# Gastroscopy-CutController_Button.net
KiCad netlist of a schematic drawn in Altium Designer
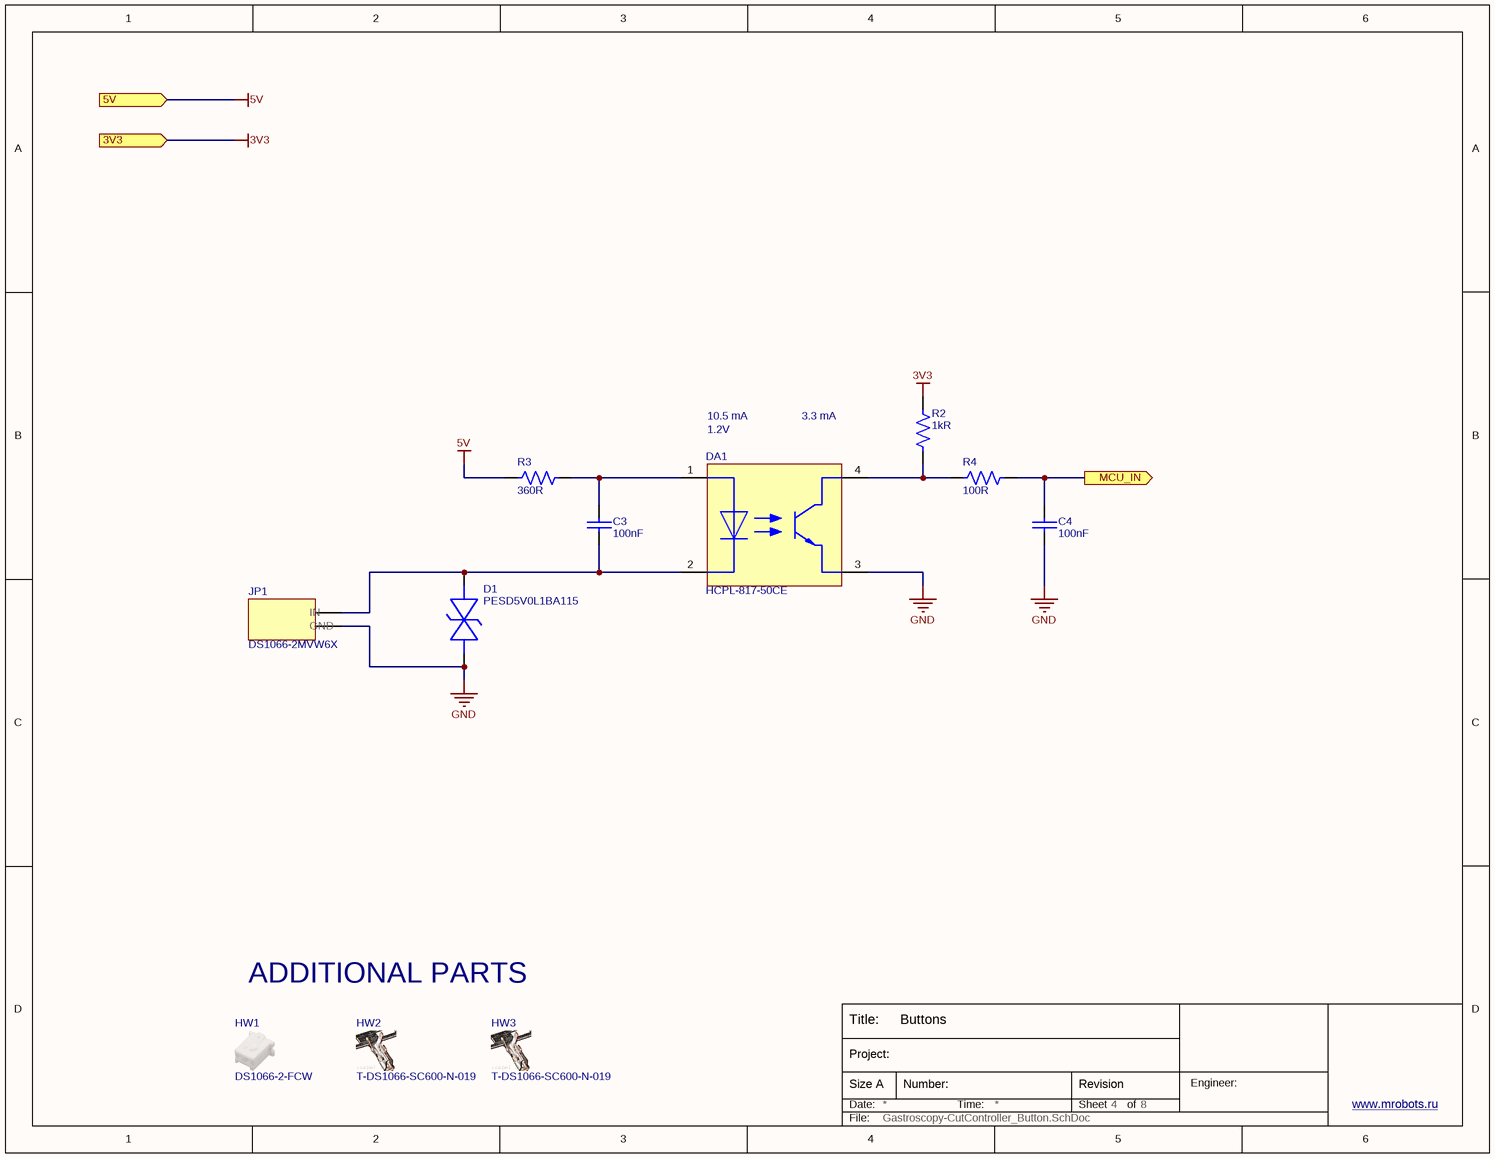
[diagram p0: Gastroscopy-CutController_Button.SchDoc]

(export (version "E")
  (design (tool "Eeschema 10.0.6"))
  (components
    (comp (ref "C3")
      (value "100nF")
      (footprint "CAP_0603")
      (description "CAP CER 0.1UF 50V X7R 0603")
      (fields (field (name "TOLERANCE") "10%"))
      (libsource (lib "Gastroscopy-Controller") (part "CL10B104KB8NNNL"))
    )
    (comp (ref "C4")
      (value "100nF")
      (footprint "CAP_0603")
      (description "CAP CER 0.1UF 50V X7R 0603")
      (fields (field (name "TOLERANCE") "10%"))
      (libsource (lib "Gastroscopy-Controller") (part "CL10B104KB8NNNL"))
    )
    (comp (ref "D1")
      (value "PESD5V0L1BA115")
      (footprint "SOD-323")
      (description "Diode Esd Prot")
      (libsource (lib "Gastroscopy-CutController") (part "PESD5V0L1BA,115"))
    )
    (comp (ref "DA1")
      (value "HCPL-817-50CE")
      (footprint "HCPL-817-50CE")
      (description "OPTOISOLATOR 5KV TRANSISTOR 4SMD")
      (libsource (lib "Gastroscopy-Controller") (part "HCPL-817-50CE"))
    )
    (comp (ref "HW1")
      (value "DS1066-2-FCW")
      (description "CONN SOCKET 2POS 2MM")
      (libsource (lib "Gastroscopy-Controller") (part "DS1066-2-FCW"))
    )
    (comp (ref "HW2")
      (value "T-DS1066-SC600-N-019")
      (description "СONNECTOR DS1066")
      (libsource (lib "Gastroscopy-Controller") (part "T-DS1066-SC600-N-019"))
    )
    (comp (ref "HW3")
      (value "T-DS1066-SC600-N-019")
      (description "СONNECTOR DS1066")
      (libsource (lib "Gastroscopy-Controller") (part "T-DS1066-SC600-N-019"))
    )
    (comp (ref "JP1")
      (value "DS1066-2MVW6X")
      (footprint "DS1066-2MVW6X")
      (description "CONN HEADER 2POS 2MM")
      (libsource (lib "Gastroscopy-Controller") (part "DS1066-2MVW6X"))
    )
    (comp (ref "R2")
      (value "1kR")
      (footprint "RES_0603")
      (description "RES 1K OHM 1% 1/10W 0603")
      (fields (field (name "TOLERANCE") "1%"))
      (libsource (lib "Gastroscopy-Controller") (part "RC0603FR-071KL"))
    )
    (comp (ref "R3")
      (value "360R")
      (footprint "RES_0603")
      (description "RES 360 OHM 1% 1/10W 0603")
      (fields (field (name "TOLERANCE") "1%"))
      (libsource (lib "Gastroscopy-Controller") (part "RC0603FR-07360RL"))
    )
    (comp (ref "R4")
      (value "100R")
      (footprint "RES_0603")
      (description "RES 100 OHM 1% 1/10W 0603")
      (fields (field (name "TOLERANCE") "1%"))
      (libsource (lib "Gastroscopy-Controller") (part "RC0603FR-07100RL"))
    )
  )
  (nets
    (net (code "1") (name "/MCU_IN") (class "Default")
      (node (ref "C4") (pin "1") (pinfunction "1_1") (pintype "passive"))
      (node (ref "R4") (pin "1") (pinfunction "1_1") (pintype "passive"))
    )
    (net (code "2") (name "3V3") (class "Default")
      (node (ref "R2") (pin "1") (pinfunction "1_1") (pintype "passive"))
    )
    (net (code "3") (name "5V") (class "Default")
      (node (ref "R3") (pin "1") (pinfunction "1_1") (pintype "passive"))
    )
    (net (code "4") (name "GND") (class "Default")
      (node (ref "C4") (pin "2") (pinfunction "2_2") (pintype "passive"))
      (node (ref "D1") (pin "2") (pinfunction "2_2") (pintype "passive"))
      (node (ref "DA1") (pin "3") (pinfunction "EMITTER_3") (pintype "passive"))
      (node (ref "JP1") (pin "2") (pinfunction "2_2") (pintype "passive"))
    )
    (net (code "5") (name "Net-(DA1-ANODE)") (class "Default")
      (node (ref "C3") (pin "1") (pinfunction "1_1") (pintype "passive"))
      (node (ref "DA1") (pin "1") (pinfunction "ANODE_1") (pintype "passive"))
      (node (ref "R3") (pin "2") (pinfunction "2_2") (pintype "passive"))
    )
    (net (code "6") (name "Net-(DA1-CATHODE)") (class "Default")
      (node (ref "C3") (pin "2") (pinfunction "2_2") (pintype "passive"))
      (node (ref "D1") (pin "1") (pinfunction "1_1") (pintype "passive"))
      (node (ref "DA1") (pin "2") (pinfunction "CATHODE_2") (pintype "passive"))
      (node (ref "JP1") (pin "1") (pinfunction "1_1") (pintype "passive"))
    )
    (net (code "7") (name "Net-(DA1-COLLECTOR)") (class "Default")
      (node (ref "DA1") (pin "4") (pinfunction "COLLECTOR_4") (pintype "passive"))
      (node (ref "R2") (pin "2") (pinfunction "2_2") (pintype "passive"))
      (node (ref "R4") (pin "2") (pinfunction "2_2") (pintype "passive"))
    )
  )
)
